# usbB_isp.net
KiCad netlist of a schematic drawn in EAGLE
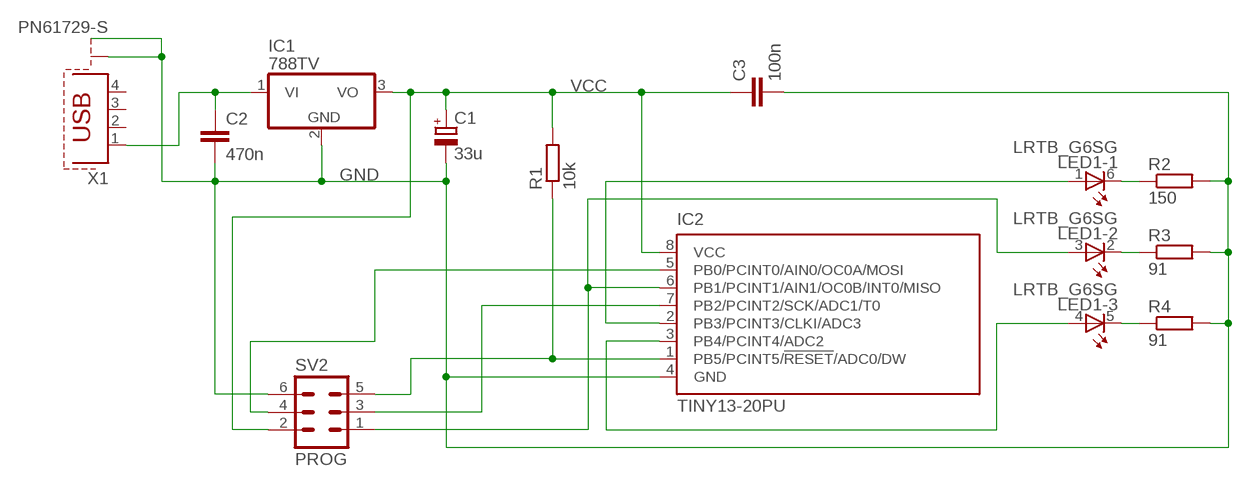
[diagram p0: schematic, sheet 1]

(export (version "E")
  (design (tool "Eeschema 10.0.6"))
  (components
    (comp (ref "C1")
      (value "33u")
      (footprint "eagle-import:E2,5-6E")
      (libsource (lib "eagle-import") (part "CPOL-EUE2,5-6E"))
    )
    (comp (ref "C2")
      (value "470n")
      (footprint "eagle-import:C050-025X075")
      (libsource (lib "eagle-import") (part "C-EU050-025X075"))
    )
    (comp (ref "C3")
      (value "100n")
      (footprint "eagle-import:C050-025X075")
      (libsource (lib "eagle-import") (part "C-EU050-025X075"))
    )
    (comp (ref "IC1")
      (value "788TV")
      (footprint "eagle-import:TO220V")
      (libsource (lib "eagle-import") (part "78TV8"))
    )
    (comp (ref "IC2")
      (value "TINY13-20PU")
      (footprint "eagle-import:DIL08")
      (fields (field (name "MPN") "ATTINY13-20PU"))
      (libsource (lib "eagle-import") (part "TINY13PU-20"))
    )
    (comp (ref "LED1")
      (value "LRTB_G6SG")
      (footprint "eagle-import:LRTB_G6SG")
      (libsource (lib "eagle-import") (part "LRTB_G6SG"))
    )
    (comp (ref "R1")
      (value "10k")
      (footprint "eagle-import:0204_7")
      (libsource (lib "eagle-import") (part "R-EU_0204/7"))
    )
    (comp (ref "R2")
      (value "150")
      (footprint "eagle-import:0204_7")
      (libsource (lib "eagle-import") (part "R-EU_0204/7"))
    )
    (comp (ref "R3")
      (value "91")
      (footprint "eagle-import:0204_7")
      (libsource (lib "eagle-import") (part "R-EU_0204/7"))
    )
    (comp (ref "R4")
      (value "91")
      (footprint "eagle-import:0204_7")
      (libsource (lib "eagle-import") (part "R-EU_0204/7"))
    )
    (comp (ref "SV2")
      (value "PROG")
      (footprint "eagle-import:ML6")
      (libsource (lib "eagle-import") (part "ML6"))
    )
    (comp (ref "X1")
      (value "PN61729-S")
      (footprint "eagle-import:PN61729-S")
      (libsource (lib "eagle-import") (part "PN61729-S"))
    )
  )
  (nets
    (net (code "1") (name "/GND") (class "Default")
      (node (ref "C1") (pin "-") (pinfunction "-_-") (pintype "passive"))
      (node (ref "C2") (pin "2") (pinfunction "2_2") (pintype "passive"))
      (node (ref "C3") (pin "2") (pinfunction "2_2") (pintype "passive"))
      (node (ref "IC1") (pin "2") (pinfunction "GND_2") (pintype "passive"))
      (node (ref "IC2") (pin "4") (pinfunction "GND_4") (pintype "power_in"))
      (node (ref "R2") (pin "2") (pinfunction "2_2") (pintype "passive"))
      (node (ref "R3") (pin "2") (pinfunction "2_2") (pintype "passive"))
      (node (ref "R4") (pin "2") (pinfunction "2_2") (pintype "passive"))
      (node (ref "SV2") (pin "6") (pinfunction "6_6") (pintype "passive"))
      (node (ref "X1") (pin "S1") (pinfunction "S1_S1") (pintype "passive"))
    )
    (net (code "2") (name "/VCC") (class "Default")
      (node (ref "C1") (pin "+") (pinfunction "+_+") (pintype "passive"))
      (node (ref "C3") (pin "1") (pinfunction "1_1") (pintype "passive"))
      (node (ref "IC1") (pin "3") (pinfunction "VO_3") (pintype "passive"))
      (node (ref "IC2") (pin "8") (pinfunction "VCC_8") (pintype "power_in"))
      (node (ref "R1") (pin "2") (pinfunction "2_2") (pintype "passive"))
      (node (ref "SV2") (pin "2") (pinfunction "2_2") (pintype "passive"))
    )
    (net (code "3") (name "Net-(IC1-VI)") (class "Default")
      (node (ref "C2") (pin "1") (pinfunction "1_1") (pintype "passive"))
      (node (ref "IC1") (pin "1") (pinfunction "VI_1") (pintype "input"))
      (node (ref "X1") (pin "1") (pinfunction "1_1") (pintype "passive"))
    )
    (net (code "4") (name "Net-(IC2-PB0{slash}PCINT0{slash}AIN0{slash}OC0A{slash}MOSI)") (class "Default")
      (node (ref "IC2") (pin "5") (pinfunction "PB0/PCINT0/AIN0/OC0A/MOSI_5") (pintype "bidirectional"))
      (node (ref "SV2") (pin "4") (pinfunction "4_4") (pintype "passive"))
    )
    (net (code "5") (name "Net-(IC2-PB1{slash}PCINT1{slash}AIN1{slash}OC0B{slash}INT0{slash}MISO)") (class "Default")
      (node (ref "IC2") (pin "6") (pinfunction "PB1/PCINT1/AIN1/OC0B/INT0/MISO_6") (pintype "bidirectional"))
      (node (ref "LED1") (pin "3") (pinfunction "A_3") (pintype "passive"))
      (node (ref "SV2") (pin "1") (pinfunction "1_1") (pintype "passive"))
    )
    (net (code "6") (name "Net-(IC2-PB2{slash}PCINT2{slash}SCK{slash}ADC1{slash}T0)") (class "Default")
      (node (ref "IC2") (pin "7") (pinfunction "PB2/PCINT2/SCK/ADC1/T0_7") (pintype "bidirectional"))
      (node (ref "SV2") (pin "3") (pinfunction "3_3") (pintype "passive"))
    )
    (net (code "7") (name "Net-(IC2-PB3{slash}PCINT3{slash}CLKI{slash}ADC3)") (class "Default")
      (node (ref "IC2") (pin "2") (pinfunction "PB3/PCINT3/CLKI/ADC3_2") (pintype "bidirectional"))
      (node (ref "LED1") (pin "1") (pinfunction "A_1") (pintype "passive"))
    )
    (net (code "8") (name "Net-(IC2-PB4{slash}PCINT4{slash}ADC2)") (class "Default")
      (node (ref "IC2") (pin "3") (pinfunction "PB4/PCINT4/ADC2_3") (pintype "bidirectional"))
      (node (ref "LED1") (pin "4") (pinfunction "A_4") (pintype "passive"))
    )
    (net (code "9") (name "Net-(IC2-PB5{slash}PCINT5{slash}~{RESET}{slash}ADC0{slash}DW)") (class "Default")
      (node (ref "IC2") (pin "1") (pinfunction "PB5/PCINT5/~{RESET}/ADC0/DW_1") (pintype "bidirectional"))
      (node (ref "R1") (pin "1") (pinfunction "1_1") (pintype "passive"))
      (node (ref "SV2") (pin "5") (pinfunction "5_5") (pintype "passive"))
    )
    (net (code "10") (name "Net-(LED1A-C)") (class "Default")
      (node (ref "LED1") (pin "6") (pinfunction "C_6") (pintype "passive"))
      (node (ref "R2") (pin "1") (pinfunction "1_1") (pintype "passive"))
    )
    (net (code "11") (name "Net-(LED1B-C)") (class "Default")
      (node (ref "LED1") (pin "2") (pinfunction "C_2") (pintype "passive"))
      (node (ref "R3") (pin "1") (pinfunction "1_1") (pintype "passive"))
    )
    (net (code "12") (name "Net-(LED1C-C)") (class "Default")
      (node (ref "LED1") (pin "5") (pinfunction "C_5") (pintype "passive"))
      (node (ref "R4") (pin "1") (pinfunction "1_1") (pintype "passive"))
    )
    (net (code "13") (name "unconnected-(X1-Pad2)") (class "Default")
      (node (ref "X1") (pin "2") (pinfunction "2_2") (pintype "passive"))
    )
    (net (code "14") (name "unconnected-(X1-Pad3)") (class "Default")
      (node (ref "X1") (pin "3") (pinfunction "3_3") (pintype "passive"))
    )
    (net (code "15") (name "unconnected-(X1-Pad4)") (class "Default")
      (node (ref "X1") (pin "4") (pinfunction "4_4") (pintype "passive"))
    )
    (net (code "16") (name "unconnected-(X1-PadS2)") (class "Default")
      (node (ref "X1") (pin "S2") (pinfunction "S2_S2") (pintype "passive"))
    )
  )
)
